# soil_temp_v0_1.net
KiCad netlist of a schematic drawn in EAGLE
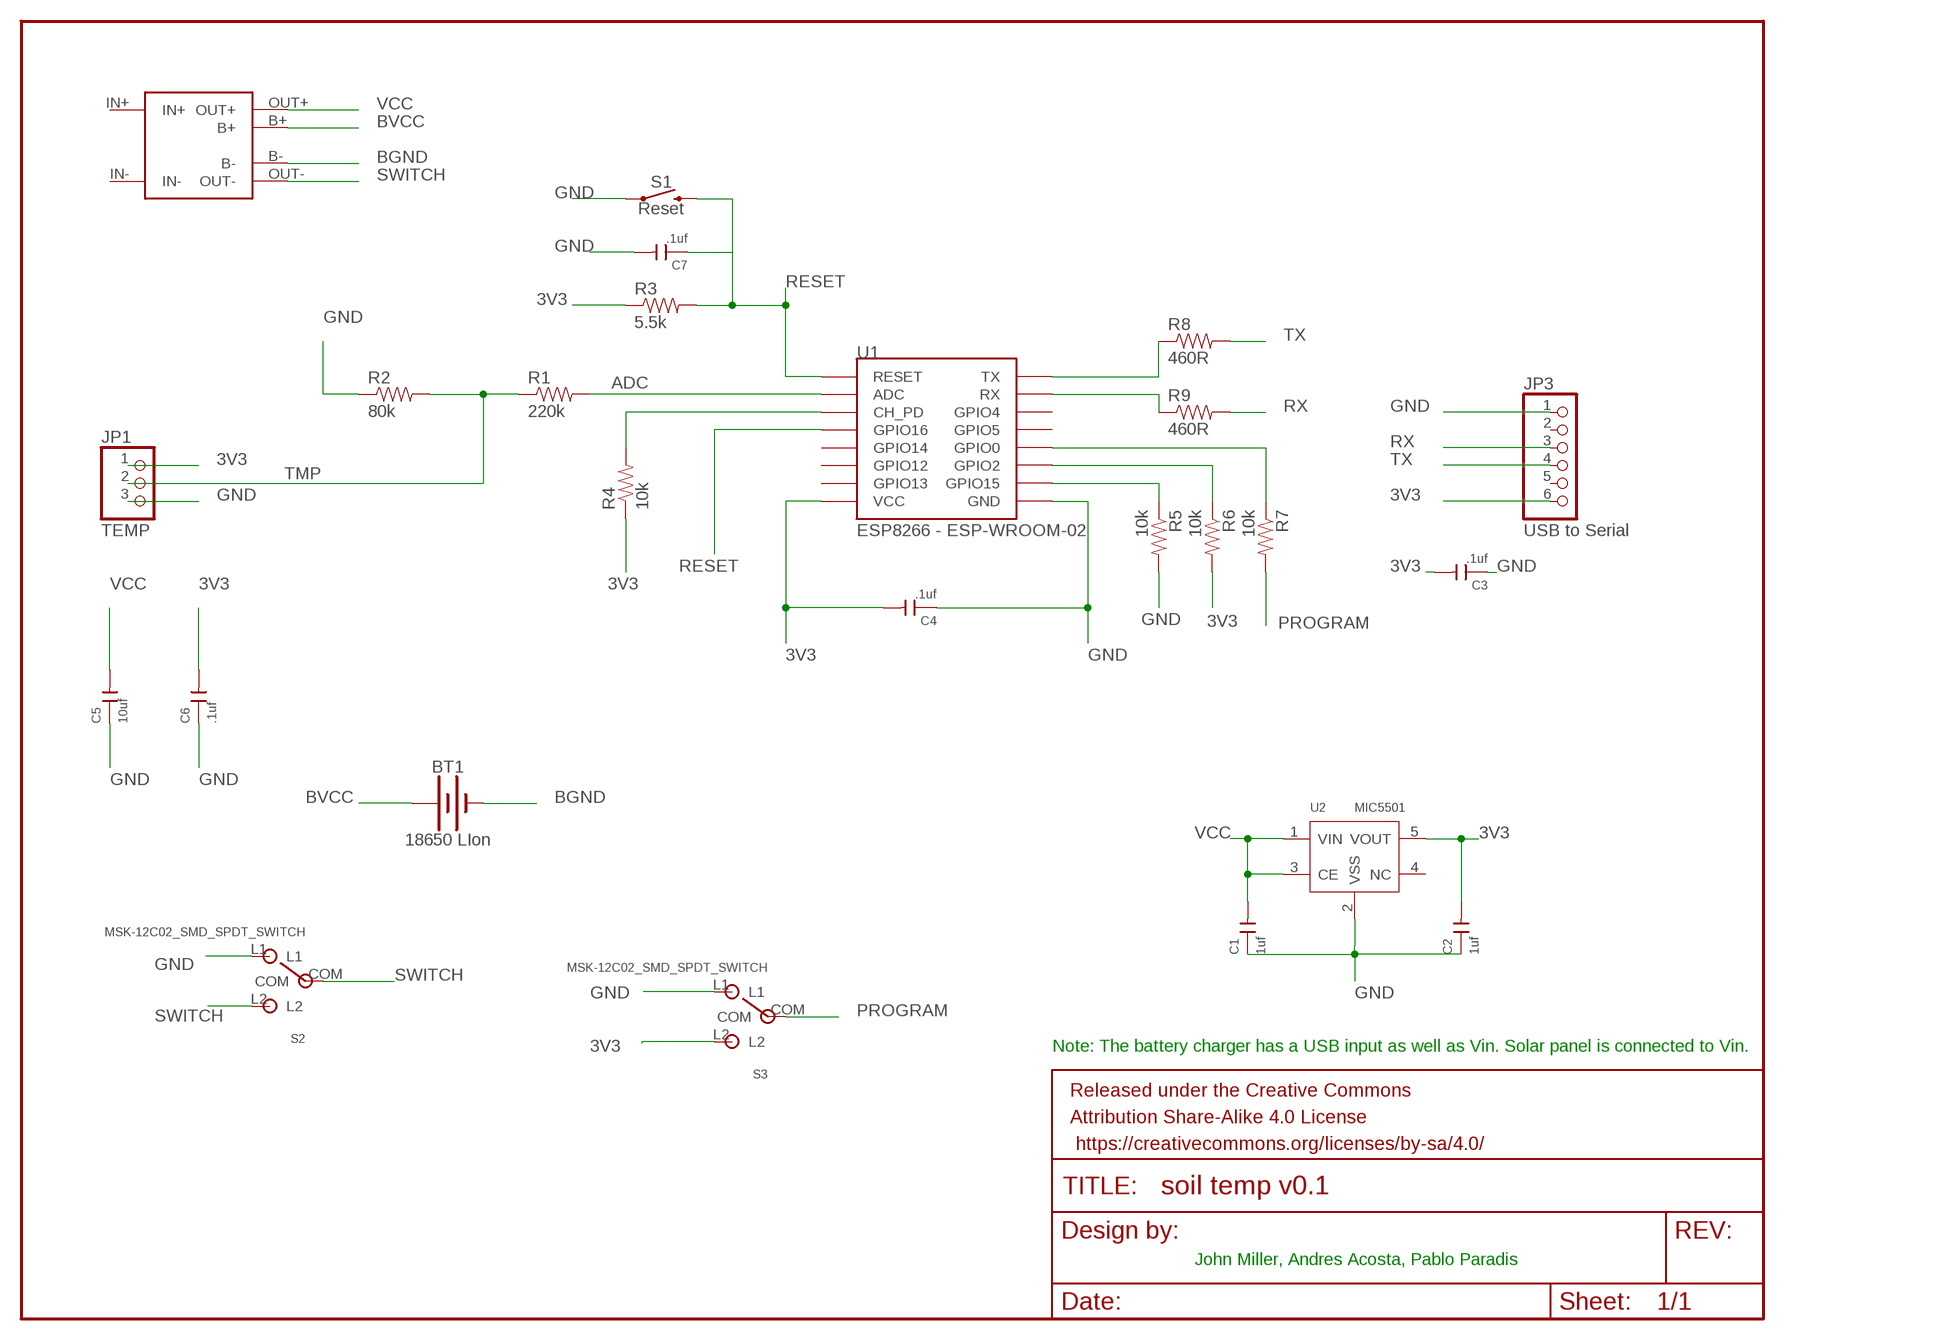
[diagram p0: schematic, sheet 1]

(export (version "E")
  (design (tool "Eeschema 10.0.6"))
  (components
    (comp (ref "BT1")
      (value "18650 LIon")
      (footprint "eagle-import:BATTERY_18650-HOLDER")
      (libsource (lib "eagle-import") (part "BATTERY-18650"))
    )
    (comp (ref "C1")
      (value "1uf")
      (footprint "eagle-import:C0805")
      (fields (field (name "MPN") "CC0805KKX7R8BB105"))
      (libsource (lib "eagle-import") (part "CERAMIC-1UF-25V-10%-X7R(0805)"))
    )
    (comp (ref "C2")
      (value "1uf")
      (footprint "eagle-import:C0805")
      (fields (field (name "MPN") "CC0805KKX7R8BB105"))
      (libsource (lib "eagle-import") (part "CERAMIC-1UF-25V-10%-X7R(0805)"))
    )
    (comp (ref "C3")
      (value ".1uf")
      (footprint "eagle-import:C0805")
      (fields (field (name "MPN") "CC0805KKX7R8BB105"))
      (libsource (lib "eagle-import") (part "CERAMIC-1UF-25V-10%-X7R(0805)"))
    )
    (comp (ref "C4")
      (value ".1uf")
      (footprint "eagle-import:C0805")
      (fields (field (name "MPN") "CC0805KKX7R8BB105"))
      (libsource (lib "eagle-import") (part "CERAMIC-1UF-25V-10%-X7R(0805)"))
    )
    (comp (ref "C5")
      (value "10uf")
      (footprint "eagle-import:C0805")
      (fields (field (name "MPN") "CC0805KKX7R8BB105"))
      (libsource (lib "eagle-import") (part "CERAMIC-1UF-25V-10%-X7R(0805)"))
    )
    (comp (ref "C6")
      (value ".1uf")
      (footprint "eagle-import:C0805")
      (fields (field (name "MPN") "CC0805KKX7R8BB105"))
      (libsource (lib "eagle-import") (part "CERAMIC-1UF-25V-10%-X7R(0805)"))
    )
    (comp (ref "C7")
      (value ".1uf")
      (footprint "eagle-import:C0805")
      (fields (field (name "MPN") "CC0805KKX7R8BB105"))
      (libsource (lib "eagle-import") (part "CERAMIC-1UF-25V-10%-X7R(0805)"))
    )
    (comp (ref "FRAME1")
      (value "FRAME-LETTERNO_PACKAGE")
      (footprint "eagle-import:DUMMY")
      (fields (field (name "DESIGNER") "Nobody"))
      (libsource (lib "eagle-import") (part "FRAME-LETTERNO_PACKAGE"))
    )
    (comp (ref "JP1")
      (value "TEMP")
      (footprint "eagle-import:1X03")
      (libsource (lib "eagle-import") (part "PINHD-1X3"))
    )
    (comp (ref "JP3")
      (value "USB to Serial")
      (footprint "eagle-import:1X06_90")
      (libsource (lib "eagle-import") (part "PINHD-1X6/90"))
    )
    (comp (ref "R1")
      (value "220k")
      (footprint "eagle-import:R0805")
      (libsource (lib "eagle-import") (part "RESISTOR0805"))
    )
    (comp (ref "R2")
      (value "80k")
      (footprint "eagle-import:R0805")
      (libsource (lib "eagle-import") (part "RESISTOR0805"))
    )
    (comp (ref "R3")
      (value "5.5k")
      (footprint "eagle-import:R0805")
      (libsource (lib "eagle-import") (part "RESISTOR0805"))
    )
    (comp (ref "R4")
      (value "10k")
      (footprint "eagle-import:R0805")
      (libsource (lib "eagle-import") (part "RESISTOR0805"))
    )
    (comp (ref "R5")
      (value "10k")
      (footprint "eagle-import:R0805")
      (libsource (lib "eagle-import") (part "RESISTOR0805"))
    )
    (comp (ref "R6")
      (value "10k")
      (footprint "eagle-import:R0805")
      (libsource (lib "eagle-import") (part "RESISTOR0805"))
    )
    (comp (ref "R7")
      (value "10k")
      (footprint "eagle-import:R0805")
      (libsource (lib "eagle-import") (part "RESISTOR0805"))
    )
    (comp (ref "R8")
      (value "460R")
      (footprint "eagle-import:R0805")
      (libsource (lib "eagle-import") (part "RESISTOR0805"))
    )
    (comp (ref "R9")
      (value "460R")
      (footprint "eagle-import:R0805")
      (libsource (lib "eagle-import") (part "RESISTOR0805"))
    )
    (comp (ref "S1")
      (value "Reset")
      (footprint "eagle-import:TACTILE_SWITCH_SMD_6.2MM_TALL")
      (libsource (lib "eagle-import") (part "MOMENTARY-SWITCH-SPST-SMD-6.2MM-TALL"))
    )
    (comp (ref "S2")
      (value "MSK-12C02_SMD_SPDT_SWITCH")
      (footprint "eagle-import:MSK-12C02")
      (libsource (lib "eagle-import") (part "MSK-12C02_SMD_SPDT_SWITCH"))
    )
    (comp (ref "S3")
      (value "MSK-12C02_SMD_SPDT_SWITCH")
      (footprint "eagle-import:MSK-12C02")
      (libsource (lib "eagle-import") (part "MSK-12C02_SMD_SPDT_SWITCH"))
    )
    (comp (ref "U1")
      (value "ESP8266 - ESP-WROOM-02")
      (footprint "eagle-import:ESP12")
      (libsource (lib "eagle-import") (part "ESP12"))
    )
    (comp (ref "U2")
      (value "MIC5501")
      (footprint "eagle-import:SOT-23-5")
      (fields (field (name "MPN") "XC6204B332MR"))
      (libsource (lib "eagle-import") (part "PMIC-LDO-XC6204B332MR(SOT23-5)"))
    )
    (comp (ref "U3")
      (value "TP4056-MODULE")
      (footprint "eagle-import:TP4056-LITHIUM-PROTECTED-MODULE")
      (libsource (lib "eagle-import") (part "TP4056-MODULE"))
    )
  )
  (nets
    (net (code "1") (name "/3V3") (class "Default")
      (node (ref "C2") (pin "2") (pinfunction "2_2") (pintype "passive"))
      (node (ref "C3") (pin "2") (pinfunction "2_2") (pintype "passive"))
      (node (ref "C4") (pin "2") (pinfunction "2_2") (pintype "passive"))
      (node (ref "C6") (pin "2") (pinfunction "2_2") (pintype "passive"))
      (node (ref "JP1") (pin "1") (pinfunction "1_1") (pintype "passive"))
      (node (ref "JP3") (pin "6") (pinfunction "6_6") (pintype "passive"))
      (node (ref "R3") (pin "1") (pinfunction "1_1") (pintype "passive"))
      (node (ref "R4") (pin "1") (pinfunction "1_1") (pintype "passive"))
      (node (ref "R6") (pin "2") (pinfunction "2_2") (pintype "passive"))
      (node (ref "S3") (pin "L2") (pinfunction "L2_L2") (pintype "bidirectional"))
      (node (ref "U1") (pin "VCC") (pinfunction "VCC_VCC") (pintype "bidirectional"))
      (node (ref "U2") (pin "5") (pinfunction "VOUT_5") (pintype "output"))
    )
    (net (code "2") (name "/ADC") (class "Default")
      (node (ref "R1") (pin "2") (pinfunction "2_2") (pintype "passive"))
      (node (ref "U1") (pin "ADC") (pinfunction "ADC_ADC") (pintype "bidirectional"))
    )
    (net (code "3") (name "/BGND") (class "Default")
      (node (ref "BT1") (pin "GND@1") (pinfunction "-_GND@1") (pintype "power_in"))
      (node (ref "U3") (pin "B-") (pinfunction "B-_B-") (pintype "power_in"))
    )
    (net (code "4") (name "/BVCC") (class "Default")
      (node (ref "BT1") (pin "PWR@1") (pinfunction "+_PWR@1") (pintype "power_in"))
      (node (ref "U3") (pin "B+") (pinfunction "B+_B+") (pintype "power_in"))
    )
    (net (code "5") (name "/GND") (class "Default")
      (node (ref "C1") (pin "1") (pinfunction "1_1") (pintype "passive"))
      (node (ref "C2") (pin "1") (pinfunction "1_1") (pintype "passive"))
      (node (ref "C3") (pin "1") (pinfunction "1_1") (pintype "passive"))
      (node (ref "C4") (pin "1") (pinfunction "1_1") (pintype "passive"))
      (node (ref "C5") (pin "1") (pinfunction "1_1") (pintype "passive"))
      (node (ref "C6") (pin "1") (pinfunction "1_1") (pintype "passive"))
      (node (ref "C7") (pin "2") (pinfunction "2_2") (pintype "passive"))
      (node (ref "JP1") (pin "3") (pinfunction "3_3") (pintype "passive"))
      (node (ref "JP3") (pin "1") (pinfunction "1_1") (pintype "passive"))
      (node (ref "R2") (pin "1") (pinfunction "1_1") (pintype "passive"))
      (node (ref "R5") (pin "2") (pinfunction "2_2") (pintype "passive"))
      (node (ref "S1") (pin "A2") (pinfunction "1_A2") (pintype "passive"))
      (node (ref "S2") (pin "L1") (pinfunction "L1_L1") (pintype "bidirectional"))
      (node (ref "S3") (pin "L1") (pinfunction "L1_L1") (pintype "bidirectional"))
      (node (ref "U1") (pin "GND") (pinfunction "GND_GND") (pintype "bidirectional"))
      (node (ref "U2") (pin "2") (pinfunction "VSS_2") (pintype "power_in"))
    )
    (net (code "6") (name "/IN+") (class "Default")
      (node (ref "U3") (pin "IN+") (pinfunction "IN+_IN+") (pintype "power_in"))
    )
    (net (code "7") (name "/IN-") (class "Default")
      (node (ref "U3") (pin "IN-") (pinfunction "IN-_IN-") (pintype "power_in"))
    )
    (net (code "8") (name "/PROGRAM") (class "Default")
      (node (ref "R7") (pin "2") (pinfunction "2_2") (pintype "passive"))
      (node (ref "S3") (pin "COM") (pinfunction "COM_COM") (pintype "bidirectional"))
    )
    (net (code "9") (name "/RESET") (class "Default")
      (node (ref "C7") (pin "1") (pinfunction "1_1") (pintype "passive"))
      (node (ref "R3") (pin "2") (pinfunction "2_2") (pintype "passive"))
      (node (ref "S1") (pin "B2") (pinfunction "2_B2") (pintype "passive"))
      (node (ref "U1") (pin "GPIO16") (pinfunction "GPIO16_GPIO16") (pintype "bidirectional"))
      (node (ref "U1") (pin "RESET") (pinfunction "RESET_RESET") (pintype "bidirectional"))
    )
    (net (code "10") (name "/RX") (class "Default")
      (node (ref "JP3") (pin "3") (pinfunction "3_3") (pintype "passive"))
      (node (ref "R9") (pin "2") (pinfunction "2_2") (pintype "passive"))
    )
    (net (code "11") (name "/SWITCH") (class "Default")
      (node (ref "S2") (pin "COM") (pinfunction "COM_COM") (pintype "bidirectional"))
      (node (ref "S2") (pin "L2") (pinfunction "L2_L2") (pintype "bidirectional"))
      (node (ref "U3") (pin "OUT-") (pinfunction "OUT-_OUT-") (pintype "power_in"))
    )
    (net (code "12") (name "/TMP") (class "Default")
      (node (ref "JP1") (pin "2") (pinfunction "2_2") (pintype "passive"))
      (node (ref "R1") (pin "1") (pinfunction "1_1") (pintype "passive"))
      (node (ref "R2") (pin "2") (pinfunction "2_2") (pintype "passive"))
    )
    (net (code "13") (name "/TX") (class "Default")
      (node (ref "JP3") (pin "4") (pinfunction "4_4") (pintype "passive"))
      (node (ref "R8") (pin "2") (pinfunction "2_2") (pintype "passive"))
    )
    (net (code "14") (name "/VCC") (class "Default")
      (node (ref "C1") (pin "2") (pinfunction "2_2") (pintype "passive"))
      (node (ref "C5") (pin "2") (pinfunction "2_2") (pintype "passive"))
      (node (ref "U2") (pin "1") (pinfunction "VIN_1") (pintype "input"))
      (node (ref "U2") (pin "3") (pinfunction "CE_3") (pintype "bidirectional"))
      (node (ref "U3") (pin "OUT+") (pinfunction "OUT+_OUT+") (pintype "power_in"))
    )
    (net (code "15") (name "Net-(R4-Pad2)") (class "Default")
      (node (ref "R4") (pin "2") (pinfunction "2_2") (pintype "passive"))
      (node (ref "U1") (pin "CH_PD") (pinfunction "CH_PD_CH_PD") (pintype "bidirectional"))
    )
    (net (code "16") (name "Net-(R5-Pad1)") (class "Default")
      (node (ref "R5") (pin "1") (pinfunction "1_1") (pintype "passive"))
      (node (ref "U1") (pin "GPIO15") (pinfunction "GPIO15_GPIO15") (pintype "bidirectional"))
    )
    (net (code "17") (name "Net-(R6-Pad1)") (class "Default")
      (node (ref "R6") (pin "1") (pinfunction "1_1") (pintype "passive"))
      (node (ref "U1") (pin "GPIO2") (pinfunction "GPIO2_GPIO2") (pintype "bidirectional"))
    )
    (net (code "18") (name "Net-(R7-Pad1)") (class "Default")
      (node (ref "R7") (pin "1") (pinfunction "1_1") (pintype "passive"))
      (node (ref "U1") (pin "GPIO0") (pinfunction "GPIO0_GPIO0") (pintype "bidirectional"))
    )
    (net (code "19") (name "Net-(R8-Pad1)") (class "Default")
      (node (ref "R8") (pin "1") (pinfunction "1_1") (pintype "passive"))
      (node (ref "U1") (pin "TX") (pinfunction "TX_TX") (pintype "bidirectional"))
    )
    (net (code "20") (name "Net-(R9-Pad1)") (class "Default")
      (node (ref "R9") (pin "1") (pinfunction "1_1") (pintype "passive"))
      (node (ref "U1") (pin "RX") (pinfunction "RX_RX") (pintype "bidirectional"))
    )
    (net (code "21") (name "unconnected-(JP3-Pad2)") (class "Default")
      (node (ref "JP3") (pin "2") (pinfunction "2_2") (pintype "passive"))
    )
    (net (code "22") (name "unconnected-(JP3-Pad5)") (class "Default")
      (node (ref "JP3") (pin "5") (pinfunction "5_5") (pintype "passive"))
    )
    (net (code "23") (name "unconnected-(U1-PadGPIO4)") (class "Default")
      (node (ref "U1") (pin "GPIO4") (pinfunction "GPIO4_GPIO4") (pintype "bidirectional"))
    )
    (net (code "24") (name "unconnected-(U1-PadGPIO5)") (class "Default")
      (node (ref "U1") (pin "GPIO5") (pinfunction "GPIO5_GPIO5") (pintype "bidirectional"))
    )
    (net (code "25") (name "unconnected-(U1-PadGPIO12)") (class "Default")
      (node (ref "U1") (pin "GPIO12") (pinfunction "GPIO12_GPIO12") (pintype "bidirectional"))
    )
    (net (code "26") (name "unconnected-(U1-PadGPIO13)") (class "Default")
      (node (ref "U1") (pin "GPIO13") (pinfunction "GPIO13_GPIO13") (pintype "bidirectional"))
    )
    (net (code "27") (name "unconnected-(U1-PadGPIO14)") (class "Default")
      (node (ref "U1") (pin "GPIO14") (pinfunction "GPIO14_GPIO14") (pintype "bidirectional"))
    )
    (net (code "28") (name "unconnected-(U2-NC-Pad4)") (class "Default")
      (node (ref "U2") (pin "4") (pinfunction "NC_4") (pintype "no_connect"))
    )
  )
)
